# Face.net
KiCad netlist of a schematic drawn in EAGLE
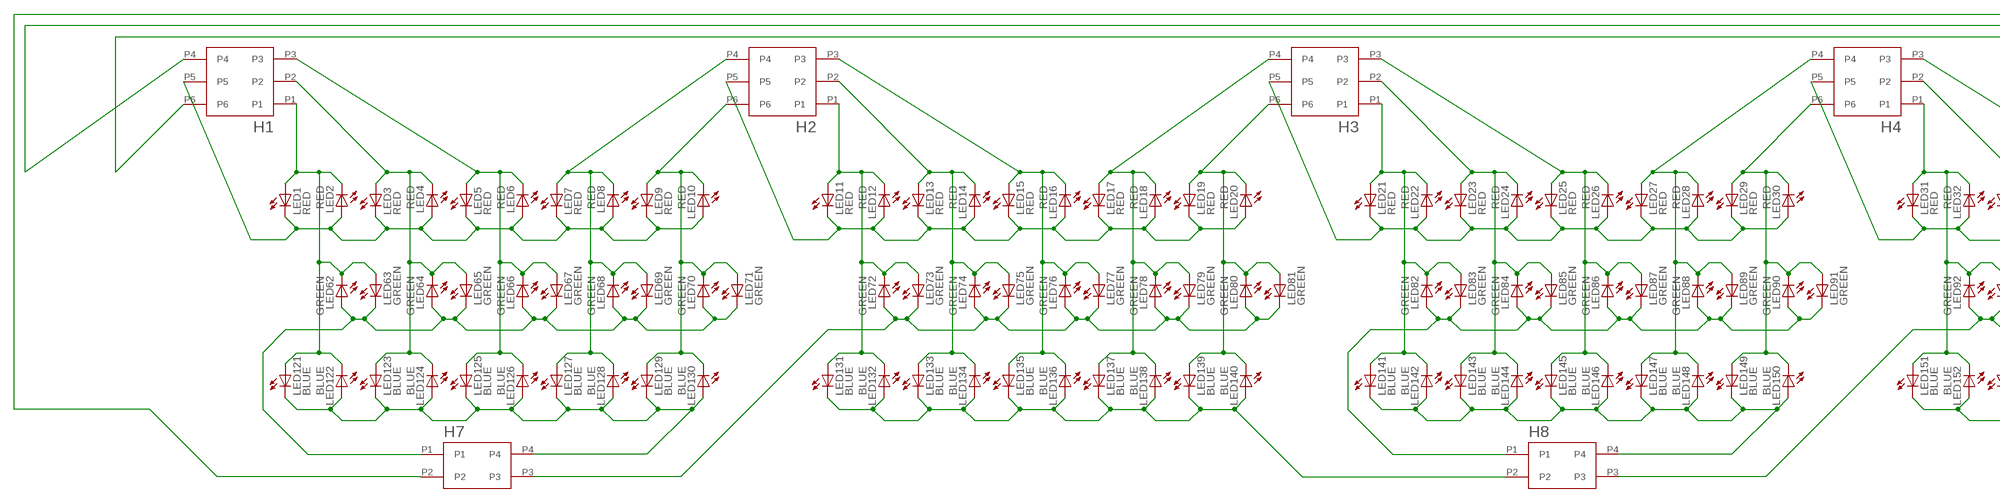
[diagram p0: schematic, sheet 1, part 1 of 2]
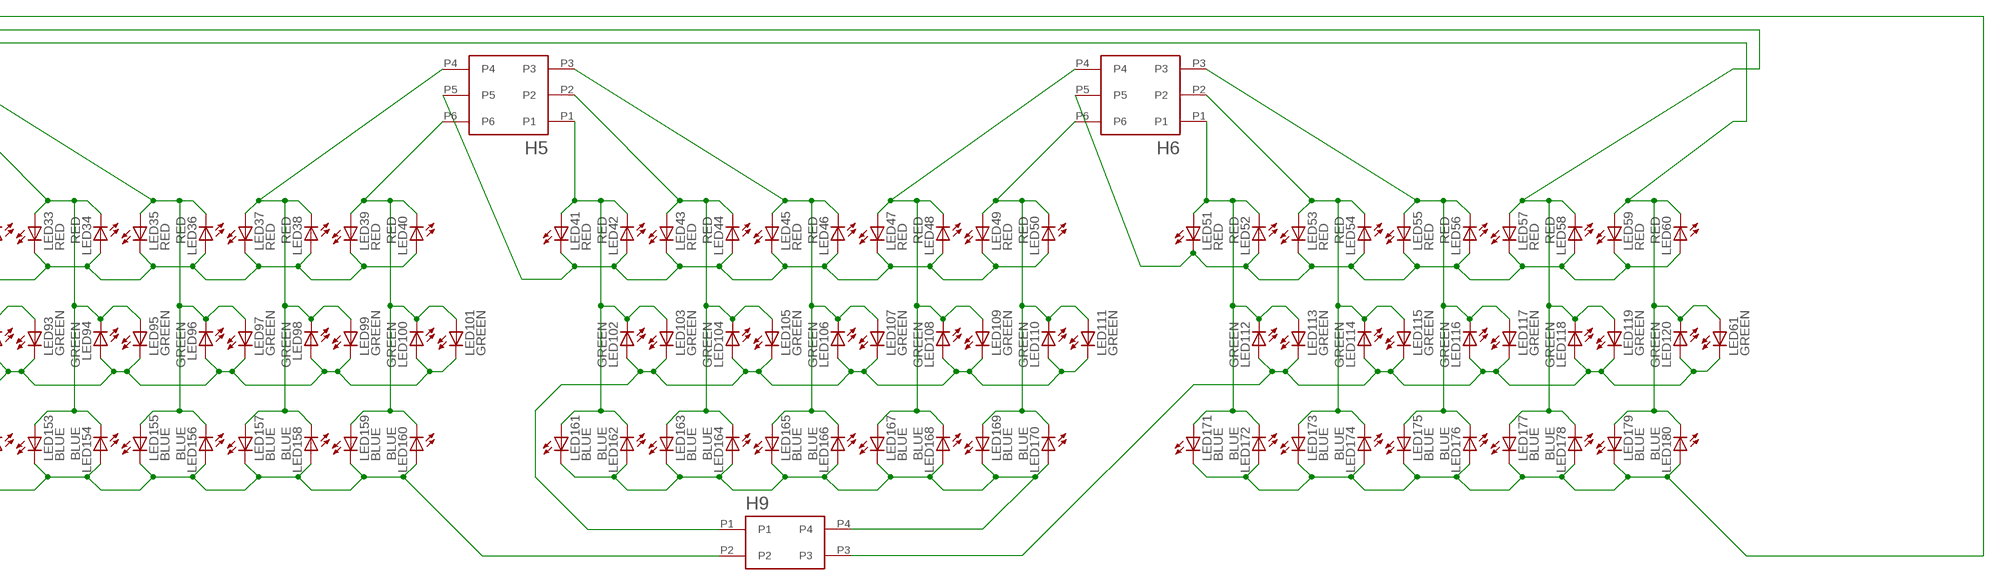
[diagram p1: schematic, sheet 1, part 2 of 2]

(export (version "E")
  (design (tool "Eeschema 10.0.6"))
  (components
    (comp (ref "H1")
      (value "2X3")
      (footprint "eagle-import:3X2_1MM_SMD")
      (libsource (lib "eagle-import") (part "2X3"))
    )
    (comp (ref "H2")
      (value "2X3")
      (footprint "eagle-import:3X2_1MM_SMD")
      (libsource (lib "eagle-import") (part "2X3"))
    )
    (comp (ref "H3")
      (value "2X3")
      (footprint "eagle-import:3X2_1MM_SMD")
      (libsource (lib "eagle-import") (part "2X3"))
    )
    (comp (ref "H4")
      (value "2X3")
      (footprint "eagle-import:3X2_1MM_SMD")
      (libsource (lib "eagle-import") (part "2X3"))
    )
    (comp (ref "H5")
      (value "2X3")
      (footprint "eagle-import:3X2_1MM_SMD")
      (libsource (lib "eagle-import") (part "2X3"))
    )
    (comp (ref "H6")
      (value "2X3")
      (footprint "eagle-import:3X2_1MM_SMD")
      (libsource (lib "eagle-import") (part "2X3"))
    )
    (comp (ref "H7")
      (value "2X2")
      (footprint "eagle-import:2X2_1MM_SMD")
      (libsource (lib "eagle-import") (part "2X2"))
    )
    (comp (ref "H8")
      (value "2X2")
      (footprint "eagle-import:2X2_1MM_SMD")
      (libsource (lib "eagle-import") (part "2X2"))
    )
    (comp (ref "H9")
      (value "2X2")
      (footprint "eagle-import:2X2_1MM_SMD")
      (libsource (lib "eagle-import") (part "2X2"))
    )
    (comp (ref "LED1")
      (value "RED")
      (footprint "eagle-import:LED-0603")
      (libsource (lib "eagle-import") (part "LED0603"))
    )
    (comp (ref "LED2")
      (value "RED")
      (footprint "eagle-import:LED-0603")
      (libsource (lib "eagle-import") (part "LED0603"))
    )
    (comp (ref "LED3")
      (value "RED")
      (footprint "eagle-import:LED-0603")
      (libsource (lib "eagle-import") (part "LED0603"))
    )
    (comp (ref "LED4")
      (value "RED")
      (footprint "eagle-import:LED-0603")
      (libsource (lib "eagle-import") (part "LED0603"))
    )
    (comp (ref "LED5")
      (value "RED")
      (footprint "eagle-import:LED-0603")
      (libsource (lib "eagle-import") (part "LED0603"))
    )
    (comp (ref "LED6")
      (value "RED")
      (footprint "eagle-import:LED-0603")
      (libsource (lib "eagle-import") (part "LED0603"))
    )
    (comp (ref "LED7")
      (value "RED")
      (footprint "eagle-import:LED-0603")
      (libsource (lib "eagle-import") (part "LED0603"))
    )
    (comp (ref "LED8")
      (value "RED")
      (footprint "eagle-import:LED-0603")
      (libsource (lib "eagle-import") (part "LED0603"))
    )
    (comp (ref "LED9")
      (value "RED")
      (footprint "eagle-import:LED-0603")
      (libsource (lib "eagle-import") (part "LED0603"))
    )
    (comp (ref "LED10")
      (value "RED")
      (footprint "eagle-import:LED-0603")
      (libsource (lib "eagle-import") (part "LED0603"))
    )
    (comp (ref "LED11")
      (value "RED")
      (footprint "eagle-import:LED-0603")
      (libsource (lib "eagle-import") (part "LED0603"))
    )
    (comp (ref "LED12")
      (value "RED")
      (footprint "eagle-import:LED-0603")
      (libsource (lib "eagle-import") (part "LED0603"))
    )
    (comp (ref "LED13")
      (value "RED")
      (footprint "eagle-import:LED-0603")
      (libsource (lib "eagle-import") (part "LED0603"))
    )
    (comp (ref "LED14")
      (value "RED")
      (footprint "eagle-import:LED-0603")
      (libsource (lib "eagle-import") (part "LED0603"))
    )
    (comp (ref "LED15")
      (value "RED")
      (footprint "eagle-import:LED-0603")
      (libsource (lib "eagle-import") (part "LED0603"))
    )
    (comp (ref "LED16")
      (value "RED")
      (footprint "eagle-import:LED-0603")
      (libsource (lib "eagle-import") (part "LED0603"))
    )
    (comp (ref "LED17")
      (value "RED")
      (footprint "eagle-import:LED-0603")
      (libsource (lib "eagle-import") (part "LED0603"))
    )
    (comp (ref "LED18")
      (value "RED")
      (footprint "eagle-import:LED-0603")
      (libsource (lib "eagle-import") (part "LED0603"))
    )
    (comp (ref "LED19")
      (value "RED")
      (footprint "eagle-import:LED-0603")
      (libsource (lib "eagle-import") (part "LED0603"))
    )
    (comp (ref "LED20")
      (value "RED")
      (footprint "eagle-import:LED-0603")
      (libsource (lib "eagle-import") (part "LED0603"))
    )
    (comp (ref "LED21")
      (value "RED")
      (footprint "eagle-import:LED-0603")
      (libsource (lib "eagle-import") (part "LED0603"))
    )
    (comp (ref "LED22")
      (value "RED")
      (footprint "eagle-import:LED-0603")
      (libsource (lib "eagle-import") (part "LED0603"))
    )
    (comp (ref "LED23")
      (value "RED")
      (footprint "eagle-import:LED-0603")
      (libsource (lib "eagle-import") (part "LED0603"))
    )
    (comp (ref "LED24")
      (value "RED")
      (footprint "eagle-import:LED-0603")
      (libsource (lib "eagle-import") (part "LED0603"))
    )
    (comp (ref "LED25")
      (value "RED")
      (footprint "eagle-import:LED-0603")
      (libsource (lib "eagle-import") (part "LED0603"))
    )
    (comp (ref "LED26")
      (value "RED")
      (footprint "eagle-import:LED-0603")
      (libsource (lib "eagle-import") (part "LED0603"))
    )
    (comp (ref "LED27")
      (value "RED")
      (footprint "eagle-import:LED-0603")
      (libsource (lib "eagle-import") (part "LED0603"))
    )
    (comp (ref "LED28")
      (value "RED")
      (footprint "eagle-import:LED-0603")
      (libsource (lib "eagle-import") (part "LED0603"))
    )
    (comp (ref "LED29")
      (value "RED")
      (footprint "eagle-import:LED-0603")
      (libsource (lib "eagle-import") (part "LED0603"))
    )
    (comp (ref "LED30")
      (value "RED")
      (footprint "eagle-import:LED-0603")
      (libsource (lib "eagle-import") (part "LED0603"))
    )
    (comp (ref "LED31")
      (value "RED")
      (footprint "eagle-import:LED-0603")
      (libsource (lib "eagle-import") (part "LED0603"))
    )
    (comp (ref "LED32")
      (value "RED")
      (footprint "eagle-import:LED-0603")
      (libsource (lib "eagle-import") (part "LED0603"))
    )
    (comp (ref "LED33")
      (value "RED")
      (footprint "eagle-import:LED-0603")
      (libsource (lib "eagle-import") (part "LED0603"))
    )
    (comp (ref "LED34")
      (value "RED")
      (footprint "eagle-import:LED-0603")
      (libsource (lib "eagle-import") (part "LED0603"))
    )
    (comp (ref "LED35")
      (value "RED")
      (footprint "eagle-import:LED-0603")
      (libsource (lib "eagle-import") (part "LED0603"))
    )
    (comp (ref "LED36")
      (value "RED")
      (footprint "eagle-import:LED-0603")
      (libsource (lib "eagle-import") (part "LED0603"))
    )
    (comp (ref "LED37")
      (value "RED")
      (footprint "eagle-import:LED-0603")
      (libsource (lib "eagle-import") (part "LED0603"))
    )
    (comp (ref "LED38")
      (value "RED")
      (footprint "eagle-import:LED-0603")
      (libsource (lib "eagle-import") (part "LED0603"))
    )
    (comp (ref "LED39")
      (value "RED")
      (footprint "eagle-import:LED-0603")
      (libsource (lib "eagle-import") (part "LED0603"))
    )
    (comp (ref "LED40")
      (value "RED")
      (footprint "eagle-import:LED-0603")
      (libsource (lib "eagle-import") (part "LED0603"))
    )
    (comp (ref "LED41")
      (value "RED")
      (footprint "eagle-import:LED-0603")
      (libsource (lib "eagle-import") (part "LED0603"))
    )
    (comp (ref "LED42")
      (value "RED")
      (footprint "eagle-import:LED-0603")
      (libsource (lib "eagle-import") (part "LED0603"))
    )
    (comp (ref "LED43")
      (value "RED")
      (footprint "eagle-import:LED-0603")
      (libsource (lib "eagle-import") (part "LED0603"))
    )
    (comp (ref "LED44")
      (value "RED")
      (footprint "eagle-import:LED-0603")
      (libsource (lib "eagle-import") (part "LED0603"))
    )
    (comp (ref "LED45")
      (value "RED")
      (footprint "eagle-import:LED-0603")
      (libsource (lib "eagle-import") (part "LED0603"))
    )
    (comp (ref "LED46")
      (value "RED")
      (footprint "eagle-import:LED-0603")
      (libsource (lib "eagle-import") (part "LED0603"))
    )
    (comp (ref "LED47")
      (value "RED")
      (footprint "eagle-import:LED-0603")
      (libsource (lib "eagle-import") (part "LED0603"))
    )
    (comp (ref "LED48")
      (value "RED")
      (footprint "eagle-import:LED-0603")
      (libsource (lib "eagle-import") (part "LED0603"))
    )
    (comp (ref "LED49")
      (value "RED")
      (footprint "eagle-import:LED-0603")
      (libsource (lib "eagle-import") (part "LED0603"))
    )
    (comp (ref "LED50")
      (value "RED")
      (footprint "eagle-import:LED-0603")
      (libsource (lib "eagle-import") (part "LED0603"))
    )
    (comp (ref "LED51")
      (value "RED")
      (footprint "eagle-import:LED-0603")
      (libsource (lib "eagle-import") (part "LED0603"))
    )
    (comp (ref "LED52")
      (value "RED")
      (footprint "eagle-import:LED-0603")
      (libsource (lib "eagle-import") (part "LED0603"))
    )
    (comp (ref "LED53")
      (value "RED")
      (footprint "eagle-import:LED-0603")
      (libsource (lib "eagle-import") (part "LED0603"))
    )
    (comp (ref "LED54")
      (value "RED")
      (footprint "eagle-import:LED-0603")
      (libsource (lib "eagle-import") (part "LED0603"))
    )
    (comp (ref "LED55")
      (value "RED")
      (footprint "eagle-import:LED-0603")
      (libsource (lib "eagle-import") (part "LED0603"))
    )
    (comp (ref "LED56")
      (value "RED")
      (footprint "eagle-import:LED-0603")
      (libsource (lib "eagle-import") (part "LED0603"))
    )
    (comp (ref "LED57")
      (value "RED")
      (footprint "eagle-import:LED-0603")
      (libsource (lib "eagle-import") (part "LED0603"))
    )
    (comp (ref "LED58")
      (value "RED")
      (footprint "eagle-import:LED-0603")
      (libsource (lib "eagle-import") (part "LED0603"))
    )
    (comp (ref "LED59")
      (value "RED")
      (footprint "eagle-import:LED-0603")
      (libsource (lib "eagle-import") (part "LED0603"))
    )
    (comp (ref "LED60")
      (value "RED")
      (footprint "eagle-import:LED-0603")
      (libsource (lib "eagle-import") (part "LED0603"))
    )
    (comp (ref "LED61")
      (value "GREEN")
      (footprint "eagle-import:LED-0603")
      (libsource (lib "eagle-import") (part "LED0603"))
    )
    (comp (ref "LED62")
      (value "GREEN")
      (footprint "eagle-import:LED-0603")
      (libsource (lib "eagle-import") (part "LED0603"))
    )
    (comp (ref "LED63")
      (value "GREEN")
      (footprint "eagle-import:LED-0603")
      (libsource (lib "eagle-import") (part "LED0603"))
    )
    (comp (ref "LED64")
      (value "GREEN")
      (footprint "eagle-import:LED-0603")
      (libsource (lib "eagle-import") (part "LED0603"))
    )
    (comp (ref "LED65")
      (value "GREEN")
      (footprint "eagle-import:LED-0603")
      (libsource (lib "eagle-import") (part "LED0603"))
    )
    (comp (ref "LED66")
      (value "GREEN")
      (footprint "eagle-import:LED-0603")
      (libsource (lib "eagle-import") (part "LED0603"))
    )
    (comp (ref "LED67")
      (value "GREEN")
      (footprint "eagle-import:LED-0603")
      (libsource (lib "eagle-import") (part "LED0603"))
    )
    (comp (ref "LED68")
      (value "GREEN")
      (footprint "eagle-import:LED-0603")
      (libsource (lib "eagle-import") (part "LED0603"))
    )
    (comp (ref "LED69")
      (value "GREEN")
      (footprint "eagle-import:LED-0603")
      (libsource (lib "eagle-import") (part "LED0603"))
    )
    (comp (ref "LED70")
      (value "GREEN")
      (footprint "eagle-import:LED-0603")
      (libsource (lib "eagle-import") (part "LED0603"))
    )
    (comp (ref "LED71")
      (value "GREEN")
      (footprint "eagle-import:LED-0603")
      (libsource (lib "eagle-import") (part "LED0603"))
    )
    (comp (ref "LED72")
      (value "GREEN")
      (footprint "eagle-import:LED-0603")
      (libsource (lib "eagle-import") (part "LED0603"))
    )
    (comp (ref "LED73")
      (value "GREEN")
      (footprint "eagle-import:LED-0603")
      (libsource (lib "eagle-import") (part "LED0603"))
    )
    (comp (ref "LED74")
      (value "GREEN")
      (footprint "eagle-import:LED-0603")
      (libsource (lib "eagle-import") (part "LED0603"))
    )
    (comp (ref "LED75")
      (value "GREEN")
      (footprint "eagle-import:LED-0603")
      (libsource (lib "eagle-import") (part "LED0603"))
    )
    (comp (ref "LED76")
      (value "GREEN")
      (footprint "eagle-import:LED-0603")
      (libsource (lib "eagle-import") (part "LED0603"))
    )
    (comp (ref "LED77")
      (value "GREEN")
      (footprint "eagle-import:LED-0603")
      (libsource (lib "eagle-import") (part "LED0603"))
    )
    (comp (ref "LED78")
      (value "GREEN")
      (footprint "eagle-import:LED-0603")
      (libsource (lib "eagle-import") (part "LED0603"))
    )
    (comp (ref "LED79")
      (value "GREEN")
      (footprint "eagle-import:LED-0603")
      (libsource (lib "eagle-import") (part "LED0603"))
    )
    (comp (ref "LED80")
      (value "GREEN")
      (footprint "eagle-import:LED-0603")
      (libsource (lib "eagle-import") (part "LED0603"))
    )
    (comp (ref "LED81")
      (value "GREEN")
      (footprint "eagle-import:LED-0603")
      (libsource (lib "eagle-import") (part "LED0603"))
    )
    (comp (ref "LED82")
      (value "GREEN")
      (footprint "eagle-import:LED-0603")
      (libsource (lib "eagle-import") (part "LED0603"))
    )
    (comp (ref "LED83")
      (value "GREEN")
      (footprint "eagle-import:LED-0603")
      (libsource (lib "eagle-import") (part "LED0603"))
    )
    (comp (ref "LED84")
      (value "GREEN")
      (footprint "eagle-import:LED-0603")
      (libsource (lib "eagle-import") (part "LED0603"))
    )
    (comp (ref "LED85")
      (value "GREEN")
      (footprint "eagle-import:LED-0603")
      (libsource (lib "eagle-import") (part "LED0603"))
    )
    (comp (ref "LED86")
      (value "GREEN")
      (footprint "eagle-import:LED-0603")
      (libsource (lib "eagle-import") (part "LED0603"))
    )
    (comp (ref "LED87")
      (value "GREEN")
      (footprint "eagle-import:LED-0603")
      (libsource (lib "eagle-import") (part "LED0603"))
    )
    (comp (ref "LED88")
      (value "GREEN")
      (footprint "eagle-import:LED-0603")
      (libsource (lib "eagle-import") (part "LED0603"))
    )
    (comp (ref "LED89")
      (value "GREEN")
      (footprint "eagle-import:LED-0603")
      (libsource (lib "eagle-import") (part "LED0603"))
    )
    (comp (ref "LED90")
      (value "GREEN")
      (footprint "eagle-import:LED-0603")
      (libsource (lib "eagle-import") (part "LED0603"))
    )
    (comp (ref "LED91")
      (value "GREEN")
      (footprint "eagle-import:LED-0603")
      (libsource (lib "eagle-import") (part "LED0603"))
    )
    (comp (ref "LED92")
      (value "GREEN")
      (footprint "eagle-import:LED-0603")
      (libsource (lib "eagle-import") (part "LED0603"))
    )
    (comp (ref "LED93")
      (value "GREEN")
      (footprint "eagle-import:LED-0603")
      (libsource (lib "eagle-import") (part "LED0603"))
    )
    (comp (ref "LED94")
      (value "GREEN")
      (footprint "eagle-import:LED-0603")
      (libsource (lib "eagle-import") (part "LED0603"))
    )
    (comp (ref "LED95")
      (value "GREEN")
      (footprint "eagle-import:LED-0603")
      (libsource (lib "eagle-import") (part "LED0603"))
    )
    (comp (ref "LED96")
      (value "GREEN")
      (footprint "eagle-import:LED-0603")
      (libsource (lib "eagle-import") (part "LED0603"))
    )
    (comp (ref "LED97")
      (value "GREEN")
      (footprint "eagle-import:LED-0603")
      (libsource (lib "eagle-import") (part "LED0603"))
    )
    (comp (ref "LED98")
      (value "GREEN")
      (footprint "eagle-import:LED-0603")
      (libsource (lib "eagle-import") (part "LED0603"))
    )
    (comp (ref "LED99")
      (value "GREEN")
      (footprint "eagle-import:LED-0603")
      (libsource (lib "eagle-import") (part "LED0603"))
    )
    (comp (ref "LED100")
      (value "GREEN")
      (footprint "eagle-import:LED-0603")
      (libsource (lib "eagle-import") (part "LED0603"))
    )
    (comp (ref "LED101")
      (value "GREEN")
      (footprint "eagle-import:LED-0603")
      (libsource (lib "eagle-import") (part "LED0603"))
    )
    (comp (ref "LED102")
      (value "GREEN")
      (footprint "eagle-import:LED-0603")
      (libsource (lib "eagle-import") (part "LED0603"))
    )
    (comp (ref "LED103")
      (value "GREEN")
      (footprint "eagle-import:LED-0603")
      (libsource (lib "eagle-import") (part "LED0603"))
    )
    (comp (ref "LED104")
      (value "GREEN")
      (footprint "eagle-import:LED-0603")
      (libsource (lib "eagle-import") (part "LED0603"))
    )
    (comp (ref "LED105")
      (value "GREEN")
      (footprint "eagle-import:LED-0603")
      (libsource (lib "eagle-import") (part "LED0603"))
    )
    (comp (ref "LED106")
      (value "GREEN")
      (footprint "eagle-import:LED-0603")
      (libsource (lib "eagle-import") (part "LED0603"))
    )
    (comp (ref "LED107")
      (value "GREEN")
      (footprint "eagle-import:LED-0603")
      (libsource (lib "eagle-import") (part "LED0603"))
    )
    (comp (ref "LED108")
      (value "GREEN")
      (footprint "eagle-import:LED-0603")
      (libsource (lib "eagle-import") (part "LED0603"))
    )
    (comp (ref "LED109")
      (value "GREEN")
      (footprint "eagle-import:LED-0603")
      (libsource (lib "eagle-import") (part "LED0603"))
    )
    (comp (ref "LED110")
      (value "GREEN")
      (footprint "eagle-import:LED-0603")
      (libsource (lib "eagle-import") (part "LED0603"))
    )
    (comp (ref "LED111")
      (value "GREEN")
      (footprint "eagle-import:LED-0603")
      (libsource (lib "eagle-import") (part "LED0603"))
    )
    (comp (ref "LED112")
      (value "GREEN")
      (footprint "eagle-import:LED-0603")
      (libsource (lib "eagle-import") (part "LED0603"))
    )
    (comp (ref "LED113")
      (value "GREEN")
      (footprint "eagle-import:LED-0603")
      (libsource (lib "eagle-import") (part "LED0603"))
    )
    (comp (ref "LED114")
      (value "GREEN")
      (footprint "eagle-import:LED-0603")
      (libsource (lib "eagle-import") (part "LED0603"))
    )
    (comp (ref "LED115")
      (value "GREEN")
      (footprint "eagle-import:LED-0603")
      (libsource (lib "eagle-import") (part "LED0603"))
    )
    (comp (ref "LED116")
      (value "GREEN")
      (footprint "eagle-import:LED-0603")
      (libsource (lib "eagle-import") (part "LED0603"))
    )
    (comp (ref "LED117")
      (value "GREEN")
      (footprint "eagle-import:LED-0603")
      (libsource (lib "eagle-import") (part "LED0603"))
    )
    (comp (ref "LED118")
      (value "GREEN")
      (footprint "eagle-import:LED-0603")
      (libsource (lib "eagle-import") (part "LED0603"))
    )
    (comp (ref "LED119")
      (value "GREEN")
      (footprint "eagle-import:LED-0603")
      (libsource (lib "eagle-import") (part "LED0603"))
    )
    (comp (ref "LED120")
      (value "GREEN")
      (footprint "eagle-import:LED-0603")
      (libsource (lib "eagle-import") (part "LED0603"))
    )
    (comp (ref "LED121")
      (value "BLUE")
      (footprint "eagle-import:LED-0603")
      (libsource (lib "eagle-import") (part "LED0603"))
    )
    (comp (ref "LED122")
      (value "BLUE")
      (footprint "eagle-import:LED-0603")
      (libsource (lib "eagle-import") (part "LED0603"))
    )
    (comp (ref "LED123")
      (value "BLUE")
      (footprint "eagle-import:LED-0603")
      (libsource (lib "eagle-import") (part "LED0603"))
    )
    (comp (ref "LED124")
      (value "BLUE")
      (footprint "eagle-import:LED-0603")
      (libsource (lib "eagle-import") (part "LED0603"))
    )
    (comp (ref "LED125")
      (value "BLUE")
      (footprint "eagle-import:LED-0603")
      (libsource (lib "eagle-import") (part "LED0603"))
    )
    (comp (ref "LED126")
      (value "BLUE")
      (footprint "eagle-import:LED-0603")
      (libsource (lib "eagle-import") (part "LED0603"))
    )
    (comp (ref "LED127")
      (value "BLUE")
      (footprint "eagle-import:LED-0603")
      (libsource (lib "eagle-import") (part "LED0603"))
    )
    (comp (ref "LED128")
      (value "BLUE")
      (footprint "eagle-import:LED-0603")
      (libsource (lib "eagle-import") (part "LED0603"))
    )
    (comp (ref "LED129")
      (value "BLUE")
      (footprint "eagle-import:LED-0603")
      (libsource (lib "eagle-import") (part "LED0603"))
    )
    (comp (ref "LED130")
      (value "BLUE")
      (footprint "eagle-import:LED-0603")
      (libsource (lib "eagle-import") (part "LED0603"))
    )
    (comp (ref "LED131")
      (value "BLUE")
      (footprint "eagle-import:LED-0603")
      (libsource (lib "eagle-import") (part "LED0603"))
    )
    (comp (ref "LED132")
      (value "BLUE")
      (footprint "eagle-import:LED-0603")
      (libsource (lib "eagle-import") (part "LED0603"))
    )
    (comp (ref "LED133")
      (value "BLUE")
      (footprint "eagle-import:LED-0603")
      (libsource (lib "eagle-import") (part "LED0603"))
    )
    (comp (ref "LED134")
      (value "BLUE")
      (footprint "eagle-import:LED-0603")
      (libsource (lib "eagle-import") (part "LED0603"))
    )
    (comp (ref "LED135")
      (value "BLUE")
      (footprint "eagle-import:LED-0603")
      (libsource (lib "eagle-import") (part "LED0603"))
    )
    (comp (ref "LED136")
      (value "BLUE")
      (footprint "eagle-import:LED-0603")
      (libsource (lib "eagle-import") (part "LED0603"))
    )
    (comp (ref "LED137")
      (value "BLUE")
      (footprint "eagle-import:LED-0603")
      (libsource (lib "eagle-import") (part "LED0603"))
    )
    (comp (ref "LED138")
      (value "BLUE")
      (footprint "eagle-import:LED-0603")
      (libsource (lib "eagle-import") (part "LED0603"))
    )
    (comp (ref "LED139")
      (value "BLUE")
      (footprint "eagle-import:LED-0603")
      (libsource (lib "eagle-import") (part "LED0603"))
    )
    (comp (ref "LED140")
      (value "BLUE")
      (footprint "eagle-import:LED-0603")
      (libsource (lib "eagle-import") (part "LED0603"))
    )
    (comp (ref "LED141")
      (value "BLUE")
      (footprint "eagle-import:LED-0603")
      (libsource (lib "eagle-import") (part "LED0603"))
    )
    (comp (ref "LED142")
      (value "BLUE")
      (footprint "eagle-import:LED-0603")
      (libsource (lib "eagle-import") (part "LED0603"))
    )
    (comp (ref "LED143")
      (value "BLUE")
      (footprint "eagle-import:LED-0603")
      (libsource (lib "eagle-import") (part "LED0603"))
    )
    (comp (ref "LED144")
      (value "BLUE")
      (footprint "eagle-import:LED-0603")
      (libsource (lib "eagle-import") (part "LED0603"))
    )
    (comp (ref "LED145")
      (value "BLUE")
      (footprint "eagle-import:LED-0603")
      (libsource (lib "eagle-import") (part "LED0603"))
    )
    (comp (ref "LED146")
      (value "BLUE")
      (footprint "eagle-import:LED-0603")
      (libsource (lib "eagle-import") (part "LED0603"))
    )
    (comp (ref "LED147")
      (value "BLUE")
      (footprint "eagle-import:LED-0603")
      (libsource (lib "eagle-import") (part "LED0603"))
    )
    (comp (ref "LED148")
      (value "BLUE")
      (footprint "eagle-import:LED-0603")
      (libsource (lib "eagle-import") (part "LED0603"))
    )
    (comp (ref "LED149")
      (value "BLUE")
      (footprint "eagle-import:LED-0603")
      (libsource (lib "eagle-import") (part "LED0603"))
    )
    (comp (ref "LED150")
      (value "BLUE")
      (footprint "eagle-import:LED-0603")
      (libsource (lib "eagle-import") (part "LED0603"))
    )
    (comp (ref "LED151")
      (value "BLUE")
      (footprint "eagle-import:LED-0603")
      (libsource (lib "eagle-import") (part "LED0603"))
    )
    (comp (ref "LED152")
      (value "BLUE")
      (footprint "eagle-import:LED-0603")
      (libsource (lib "eagle-import") (part "LED0603"))
    )
    (comp (ref "LED153")
      (value "BLUE")
      (footprint "eagle-import:LED-0603")
      (libsource (lib "eagle-import") (part "LED0603"))
    )
    (comp (ref "LED154")
      (value "BLUE")
      (footprint "eagle-import:LED-0603")
      (libsource (lib "eagle-import") (part "LED0603"))
    )
    (comp (ref "LED155")
      (value "BLUE")
      (footprint "eagle-import:LED-0603")
      (libsource (lib "eagle-import") (part "LED0603"))
    )
    (comp (ref "LED156")
      (value "BLUE")
      (footprint "eagle-import:LED-0603")
      (libsource (lib "eagle-import") (part "LED0603"))
    )
    (comp (ref "LED157")
      (value "BLUE")
      (footprint "eagle-import:LED-0603")
      (libsource (lib "eagle-import") (part "LED0603"))
    )
    (comp (ref "LED158")
      (value "BLUE")
      (footprint "eagle-import:LED-0603")
      (libsource (lib "eagle-import") (part "LED0603"))
    )
    (comp (ref "LED159")
      (value "BLUE")
      (footprint "eagle-import:LED-0603")
      (libsource (lib "eagle-import") (part "LED0603"))
    )
    (comp (ref "LED160")
      (value "BLUE")
      (footprint "eagle-import:LED-0603")
      (libsource (lib "eagle-import") (part "LED0603"))
    )
    (comp (ref "LED161")
      (value "BLUE")
      (footprint "eagle-import:LED-0603")
      (libsource (lib "eagle-import") (part "LED0603"))
    )
    (comp (ref "LED162")
      (value "BLUE")
      (footprint "eagle-import:LED-0603")
      (libsource (lib "eagle-import") (part "LED0603"))
    )
    (comp (ref "LED163")
      (value "BLUE")
      (footprint "eagle-import:LED-0603")
      (libsource (lib "eagle-import") (part "LED0603"))
    )
    (comp (ref "LED164")
      (value "BLUE")
      (footprint "eagle-import:LED-0603")
      (libsource (lib "eagle-import") (part "LED0603"))
    )
    (comp (ref "LED165")
      (value "BLUE")
      (footprint "eagle-import:LED-0603")
      (libsource (lib "eagle-import") (part "LED0603"))
    )
    (comp (ref "LED166")
      (value "BLUE")
      (footprint "eagle-import:LED-0603")
      (libsource (lib "eagle-import") (part "LED0603"))
    )
    (comp (ref "LED167")
      (value "BLUE")
      (footprint "eagle-import:LED-0603")
      (libsource (lib "eagle-import") (part "LED0603"))
    )
    (comp (ref "LED168")
      (value "BLUE")
      (footprint "eagle-import:LED-0603")
      (libsource (lib "eagle-import") (part "LED0603"))
    )
    (comp (ref "LED169")
      (value "BLUE")
      (footprint "eagle-import:LED-0603")
      (libsource (lib "eagle-import") (part "LED0603"))
    )
    (comp (ref "LED170")
      (value "BLUE")
      (footprint "eagle-import:LED-0603")
      (libsource (lib "eagle-import") (part "LED0603"))
    )
    (comp (ref "LED171")
      (value "BLUE")
      (footprint "eagle-import:LED-0603")
      (libsource (lib "eagle-import") (part "LED0603"))
    )
    (comp (ref "LED172")
      (value "BLUE")
      (footprint "eagle-import:LED-0603")
      (libsource (lib "eagle-import") (part "LED0603"))
    )
    (comp (ref "LED173")
      (value "BLUE")
      (footprint "eagle-import:LED-0603")
      (libsource (lib "eagle-import") (part "LED0603"))
    )
    (comp (ref "LED174")
      (value "BLUE")
      (footprint "eagle-import:LED-0603")
      (libsource (lib "eagle-import") (part "LED0603"))
    )
    (comp (ref "LED175")
      (value "BLUE")
      (footprint "eagle-import:LED-0603")
      (libsource (lib "eagle-import") (part "LED0603"))
    )
    (comp (ref "LED176")
      (value "BLUE")
      (footprint "eagle-import:LED-0603")
      (libsource (lib "eagle-import") (part "LED0603"))
    )
    (comp (ref "LED177")
      (value "BLUE")
      (footprint "eagle-import:LED-0603")
      (libsource (lib "eagle-import") (part "LED0603"))
    )
    (comp (ref "LED178")
      (value "BLUE")
      (footprint "eagle-import:LED-0603")
      (libsource (lib "eagle-import") (part "LED0603"))
    )
    (comp (ref "LED179")
      (value "BLUE")
      (footprint "eagle-import:LED-0603")
      (libsource (lib "eagle-import") (part "LED0603"))
    )
    (comp (ref "LED180")
      (value "BLUE")
      (footprint "eagle-import:LED-0603")
      (libsource (lib "eagle-import") (part "LED0603"))
    )
  )
  (nets
    (net (code "1") (name "Net-(H1-PadP1)") (class "Default")
      (node (ref "H1") (pin "P1") (pinfunction "P1_P1") (pintype "bidirectional"))
      (node (ref "LED1") (pin "A") (pinfunction "A_A") (pintype "passive"))
      (node (ref "LED121") (pin "A") (pinfunction "A_A") (pintype "passive"))
      (node (ref "LED122") (pin "C") (pinfunction "C_C") (pintype "passive"))
      (node (ref "LED2") (pin "C") (pinfunction "C_C") (pintype "passive"))
      (node (ref "LED62") (pin "C") (pinfunction "C_C") (pintype "passive"))
      (node (ref "LED63") (pin "A") (pinfunction "A_A") (pintype "passive"))
    )
    (net (code "2") (name "Net-(H1-PadP2)") (class "Default")
      (node (ref "H1") (pin "P2") (pinfunction "P2_P2") (pintype "bidirectional"))
      (node (ref "LED123") (pin "A") (pinfunction "A_A") (pintype "passive"))
      (node (ref "LED124") (pin "C") (pinfunction "C_C") (pintype "passive"))
      (node (ref "LED3") (pin "A") (pinfunction "A_A") (pintype "passive"))
      (node (ref "LED4") (pin "C") (pinfunction "C_C") (pintype "passive"))
      (node (ref "LED64") (pin "C") (pinfunction "C_C") (pintype "passive"))
      (node (ref "LED65") (pin "A") (pinfunction "A_A") (pintype "passive"))
    )
    (net (code "3") (name "Net-(H1-PadP3)") (class "Default")
      (node (ref "H1") (pin "P3") (pinfunction "P3_P3") (pintype "bidirectional"))
      (node (ref "LED125") (pin "A") (pinfunction "A_A") (pintype "passive"))
      (node (ref "LED126") (pin "C") (pinfunction "C_C") (pintype "passive"))
      (node (ref "LED5") (pin "A") (pinfunction "A_A") (pintype "passive"))
      (node (ref "LED6") (pin "C") (pinfunction "C_C") (pintype "passive"))
      (node (ref "LED66") (pin "C") (pinfunction "C_C") (pintype "passive"))
      (node (ref "LED67") (pin "A") (pinfunction "A_A") (pintype "passive"))
    )
    (net (code "4") (name "Net-(H1-PadP4)") (class "Default")
      (node (ref "H1") (pin "P4") (pinfunction "P4_P4") (pintype "bidirectional"))
      (node (ref "LED118") (pin "C") (pinfunction "C_C") (pintype "passive"))
      (node (ref "LED119") (pin "A") (pinfunction "A_A") (pintype "passive"))
      (node (ref "LED177") (pin "A") (pinfunction "A_A") (pintype "passive"))
      (node (ref "LED178") (pin "C") (pinfunction "C_C") (pintype "passive"))
      (node (ref "LED57") (pin "A") (pinfunction "A_A") (pintype "passive"))
      (node (ref "LED58") (pin "C") (pinfunction "C_C") (pintype "passive"))
    )
    (net (code "5") (name "Net-(H1-PadP5)") (class "Default")
      (node (ref "H1") (pin "P5") (pinfunction "P5_P5") (pintype "bidirectional"))
      (node (ref "LED1") (pin "C") (pinfunction "C_C") (pintype "passive"))
      (node (ref "LED10") (pin "A") (pinfunction "A_A") (pintype "passive"))
      (node (ref "LED2") (pin "A") (pinfunction "A_A") (pintype "passive"))
      (node (ref "LED3") (pin "C") (pinfunction "C_C") (pintype "passive"))
      (node (ref "LED4") (pin "A") (pinfunction "A_A") (pintype "passive"))
      (node (ref "LED5") (pin "C") (pinfunction "C_C") (pintype "passive"))
      (node (ref "LED6") (pin "A") (pinfunction "A_A") (pintype "passive"))
      (node (ref "LED7") (pin "C") (pinfunction "C_C") (pintype "passive"))
      (node (ref "LED8") (pin "A") (pinfunction "A_A") (pintype "passive"))
      (node (ref "LED9") (pin "C") (pinfunction "C_C") (pintype "passive"))
    )
    (net (code "6") (name "Net-(H1-PadP6)") (class "Default")
      (node (ref "H1") (pin "P6") (pinfunction "P6_P6") (pintype "bidirectional"))
      (node (ref "LED120") (pin "C") (pinfunction "C_C") (pintype "passive"))
      (node (ref "LED179") (pin "A") (pinfunction "A_A") (pintype "passive"))
      (node (ref "LED180") (pin "C") (pinfunction "C_C") (pintype "passive"))
      (node (ref "LED59") (pin "A") (pinfunction "A_A") (pintype "passive"))
      (node (ref "LED60") (pin "C") (pinfunction "C_C") (pintype "passive"))
      (node (ref "LED61") (pin "A") (pinfunction "A_A") (pintype "passive"))
    )
    (net (code "7") (name "Net-(H2-PadP1)") (class "Default")
      (node (ref "H2") (pin "P1") (pinfunction "P1_P1") (pintype "bidirectional"))
      (node (ref "LED11") (pin "A") (pinfunction "A_A") (pintype "passive"))
      (node (ref "LED12") (pin "C") (pinfunction "C_C") (pintype "passive"))
      (node (ref "LED131") (pin "A") (pinfunction "A_A") (pintype "passive"))
      (node (ref "LED132") (pin "C") (pinfunction "C_C") (pintype "passive"))
      (node (ref "LED72") (pin "C") (pinfunction "C_C") (pintype "passive"))
      (node (ref "LED73") (pin "A") (pinfunction "A_A") (pintype "passive"))
    )
    (net (code "8") (name "Net-(H2-PadP2)") (class "Default")
      (node (ref "H2") (pin "P2") (pinfunction "P2_P2") (pintype "bidirectional"))
      (node (ref "LED13") (pin "A") (pinfunction "A_A") (pintype "passive"))
      (node (ref "LED133") (pin "A") (pinfunction "A_A") (pintype "passive"))
      (node (ref "LED134") (pin "C") (pinfunction "C_C") (pintype "passive"))
      (node (ref "LED14") (pin "C") (pinfunction "C_C") (pintype "passive"))
      (node (ref "LED74") (pin "C") (pinfunction "C_C") (pintype "passive"))
      (node (ref "LED75") (pin "A") (pinfunction "A_A") (pintype "passive"))
    )
    (net (code "9") (name "Net-(H2-PadP3)") (class "Default")
      (node (ref "H2") (pin "P3") (pinfunction "P3_P3") (pintype "bidirectional"))
      (node (ref "LED135") (pin "A") (pinfunction "A_A") (pintype "passive"))
      (node (ref "LED136") (pin "C") (pinfunction "C_C") (pintype "passive"))
      (node (ref "LED15") (pin "A") (pinfunction "A_A") (pintype "passive"))
      (node (ref "LED16") (pin "C") (pinfunction "C_C") (pintype "passive"))
      (node (ref "LED76") (pin "C") (pinfunction "C_C") (pintype "passive"))
      (node (ref "LED77") (pin "A") (pinfunction "A_A") (pintype "passive"))
    )
    (net (code "10") (name "Net-(H2-PadP4)") (class "Default")
      (node (ref "H2") (pin "P4") (pinfunction "P4_P4") (pintype "bidirectional"))
      (node (ref "LED127") (pin "A") (pinfunction "A_A") (pintype "passive"))
      (node (ref "LED128") (pin "C") (pinfunction "C_C") (pintype "passive"))
      (node (ref "LED68") (pin "C") (pinfunction "C_C") (pintype "passive"))
      (node (ref "LED69") (pin "A") (pinfunction "A_A") (pintype "passive"))
      (node (ref "LED7") (pin "A") (pinfunction "A_A") (pintype "passive"))
      (node (ref "LED8") (pin "C") (pinfunction "C_C") (pintype "passive"))
    )
    (net (code "11") (name "Net-(H2-PadP5)") (class "Default")
      (node (ref "H2") (pin "P5") (pinfunction "P5_P5") (pintype "bidirectional"))
      (node (ref "LED11") (pin "C") (pinfunction "C_C") (pintype "passive"))
      (node (ref "LED12") (pin "A") (pinfunction "A_A") (pintype "passive"))
      (node (ref "LED13") (pin "C") (pinfunction "C_C") (pintype "passive"))
      (node (ref "LED14") (pin "A") (pinfunction "A_A") (pintype "passive"))
      (node (ref "LED15") (pin "C") (pinfunction "C_C") (pintype "passive"))
      (node (ref "LED16") (pin "A") (pinfunction "A_A") (pintype "passive"))
      (node (ref "LED17") (pin "C") (pinfunction "C_C") (pintype "passive"))
      (node (ref "LED18") (pin "A") (pinfunction "A_A") (pintype "passive"))
      (node (ref "LED19") (pin "C") (pinfunction "C_C") (pintype "passive"))
      (node (ref "LED20") (pin "A") (pinfunction "A_A") (pintype "passive"))
    )
    (net (code "12") (name "Net-(H2-PadP6)") (class "Default")
      (node (ref "H2") (pin "P6") (pinfunction "P6_P6") (pintype "bidirectional"))
      (node (ref "LED10") (pin "C") (pinfunction "C_C") (pintype "passive"))
      (node (ref "LED129") (pin "A") (pinfunction "A_A") (pintype "passive"))
      (node (ref "LED130") (pin "C") (pinfunction "C_C") (pintype "passive"))
      (node (ref "LED70") (pin "C") (pinfunction "C_C") (pintype "passive"))
      (node (ref "LED71") (pin "A") (pinfunction "A_A") (pintype "passive"))
      (node (ref "LED9") (pin "A") (pinfunction "A_A") (pintype "passive"))
    )
    (net (code "13") (name "Net-(H3-PadP1)") (class "Default")
      (node (ref "H3") (pin "P1") (pinfunction "P1_P1") (pintype "bidirectional"))
      (node (ref "LED141") (pin "A") (pinfunction "A_A") (pintype "passive"))
      (node (ref "LED142") (pin "C") (pinfunction "C_C") (pintype "passive"))
      (node (ref "LED21") (pin "A") (pinfunction "A_A") (pintype "passive"))
      (node (ref "LED22") (pin "C") (pinfunction "C_C") (pintype "passive"))
      (node (ref "LED82") (pin "C") (pinfunction "C_C") (pintype "passive"))
      (node (ref "LED83") (pin "A") (pinfunction "A_A") (pintype "passive"))
    )
    (net (code "14") (name "Net-(H3-PadP2)") (class "Default")
      (node (ref "H3") (pin "P2") (pinfunction "P2_P2") (pintype "bidirectional"))
      (node (ref "LED143") (pin "A") (pinfunction "A_A") (pintype "passive"))
      (node (ref "LED144") (pin "C") (pinfunction "C_C") (pintype "passive"))
      (node (ref "LED23") (pin "A") (pinfunction "A_A") (pintype "passive"))
      (node (ref "LED24") (pin "C") (pinfunction "C_C") (pintype "passive"))
      (node (ref "LED84") (pin "C") (pinfunction "C_C") (pintype "passive"))
      (node (ref "LED85") (pin "A") (pinfunction "A_A") (pintype "passive"))
    )
    (net (code "15") (name "Net-(H3-PadP3)") (class "Default")
      (node (ref "H3") (pin "P3") (pinfunction "P3_P3") (pintype "bidirectional"))
      (node (ref "LED145") (pin "A") (pinfunction "A_A") (pintype "passive"))
      (node (ref "LED146") (pin "C") (pinfunction "C_C") (pintype "passive"))
      (node (ref "LED25") (pin "A") (pinfunction "A_A") (pintype "passive"))
      (node (ref "LED26") (pin "C") (pinfunction "C_C") (pintype "passive"))
      (node (ref "LED86") (pin "C") (pinfunction "C_C") (pintype "passive"))
      (node (ref "LED87") (pin "A") (pinfunction "A_A") (pintype "passive"))
    )
    (net (code "16") (name "Net-(H3-PadP4)") (class "Default")
      (node (ref "H3") (pin "P4") (pinfunction "P4_P4") (pintype "bidirectional"))
      (node (ref "LED137") (pin "A") (pinfunction "A_A") (pintype "passive"))
      (node (ref "LED138") (pin "C") (pinfunction "C_C") (pintype "passive"))
      (node (ref "LED17") (pin "A") (pinfunction "A_A") (pintype "passive"))
      (node (ref "LED18") (pin "C") (pinfunction "C_C") (pintype "passive"))
      (node (ref "LED78") (pin "C") (pinfunction "C_C") (pintype "passive"))
      (node (ref "LED79") (pin "A") (pinfunction "A_A") (pintype "passive"))
    )
    (net (code "17") (name "Net-(H3-PadP5)") (class "Default")
      (node (ref "H3") (pin "P5") (pinfunction "P5_P5") (pintype "bidirectional"))
      (node (ref "LED21") (pin "C") (pinfunction "C_C") (pintype "passive"))
      (node (ref "LED22") (pin "A") (pinfunction "A_A") (pintype "passive"))
      (node (ref "LED23") (pin "C") (pinfunction "C_C") (pintype "passive"))
      (node (ref "LED24") (pin "A") (pinfunction "A_A") (pintype "passive"))
      (node (ref "LED25") (pin "C") (pinfunction "C_C") (pintype "passive"))
      (node (ref "LED26") (pin "A") (pinfunction "A_A") (pintype "passive"))
      (node (ref "LED27") (pin "C") (pinfunction "C_C") (pintype "passive"))
      (node (ref "LED28") (pin "A") (pinfunction "A_A") (pintype "passive"))
      (node (ref "LED29") (pin "C") (pinfunction "C_C") (pintype "passive"))
      (node (ref "LED30") (pin "A") (pinfunction "A_A") (pintype "passive"))
    )
    (net (code "18") (name "Net-(H3-PadP6)") (class "Default")
      (node (ref "H3") (pin "P6") (pinfunction "P6_P6") (pintype "bidirectional"))
      (node (ref "LED139") (pin "A") (pinfunction "A_A") (pintype "passive"))
      (node (ref "LED140") (pin "C") (pinfunction "C_C") (pintype "passive"))
      (node (ref "LED19") (pin "A") (pinfunction "A_A") (pintype "passive"))
      (node (ref "LED20") (pin "C") (pinfunction "C_C") (pintype "passive"))
      (node (ref "LED80") (pin "C") (pinfunction "C_C") (pintype "passive"))
      (node (ref "LED81") (pin "A") (pinfunction "A_A") (pintype "passive"))
    )
    (net (code "19") (name "Net-(H4-PadP1)") (class "Default")
      (node (ref "H4") (pin "P1") (pinfunction "P1_P1") (pintype "bidirectional"))
      (node (ref "LED151") (pin "A") (pinfunction "A_A") (pintype "passive"))
      (node (ref "LED152") (pin "C") (pinfunction "C_C") (pintype "passive"))
      (node (ref "LED31") (pin "A") (pinfunction "A_A") (pintype "passive"))
      (node (ref "LED32") (pin "C") (pinfunction "C_C") (pintype "passive"))
      (node (ref "LED92") (pin "C") (pinfunction "C_C") (pintype "passive"))
      (node (ref "LED93") (pin "A") (pinfunction "A_A") (pintype "passive"))
    )
    (net (code "20") (name "Net-(H4-PadP2)") (class "Default")
      (node (ref "H4") (pin "P2") (pinfunction "P2_P2") (pintype "bidirectional"))
      (node (ref "LED153") (pin "A") (pinfunction "A_A") (pintype "passive"))
      (node (ref "LED154") (pin "C") (pinfunction "C_C") (pintype "passive"))
      (node (ref "LED33") (pin "A") (pinfunction "A_A") (pintype "passive"))
      (node (ref "LED34") (pin "C") (pinfunction "C_C") (pintype "passive"))
      (node (ref "LED94") (pin "C") (pinfunction "C_C") (pintype "passive"))
      (node (ref "LED95") (pin "A") (pinfunction "A_A") (pintype "passive"))
    )
    (net (code "21") (name "Net-(H4-PadP3)") (class "Default")
      (node (ref "H4") (pin "P3") (pinfunction "P3_P3") (pintype "bidirectional"))
      (node (ref "LED155") (pin "A") (pinfunction "A_A") (pintype "passive"))
      (node (ref "LED156") (pin "C") (pinfunction "C_C") (pintype "passive"))
      (node (ref "LED35") (pin "A") (pinfunction "A_A") (pintype "passive"))
      (node (ref "LED36") (pin "C") (pinfunction "C_C") (pintype "passive"))
      (node (ref "LED96") (pin "C") (pinfunction "C_C") (pintype "passive"))
      (node (ref "LED97") (pin "A") (pinfunction "A_A") (pintype "passive"))
    )
    (net (code "22") (name "Net-(H4-PadP4)") (class "Default")
      (node (ref "H4") (pin "P4") (pinfunction "P4_P4") (pintype "bidirectional"))
      (node (ref "LED147") (pin "A") (pinfunction "A_A") (pintype "passive"))
      (node (ref "LED148") (pin "C") (pinfunction "C_C") (pintype "passive"))
      (node (ref "LED27") (pin "A") (pinfunction "A_A") (pintype "passive"))
      (node (ref "LED28") (pin "C") (pinfunction "C_C") (pintype "passive"))
      (node (ref "LED88") (pin "C") (pinfunction "C_C") (pintype "passive"))
      (node (ref "LED89") (pin "A") (pinfunction "A_A") (pintype "passive"))
    )
    (net (code "23") (name "Net-(H4-PadP5)") (class "Default")
      (node (ref "H4") (pin "P5") (pinfunction "P5_P5") (pintype "bidirectional"))
      (node (ref "LED31") (pin "C") (pinfunction "C_C") (pintype "passive"))
      (node (ref "LED32") (pin "A") (pinfunction "A_A") (pintype "passive"))
      (node (ref "LED33") (pin "C") (pinfunction "C_C") (pintype "passive"))
      (node (ref "LED34") (pin "A") (pinfunction "A_A") (pintype "passive"))
      (node (ref "LED35") (pin "C") (pinfunction "C_C") (pintype "passive"))
      (node (ref "LED36") (pin "A") (pinfunction "A_A") (pintype "passive"))
      (node (ref "LED37") (pin "C") (pinfunction "C_C") (pintype "passive"))
      (node (ref "LED38") (pin "A") (pinfunction "A_A") (pintype "passive"))
      (node (ref "LED39") (pin "C") (pinfunction "C_C") (pintype "passive"))
      (node (ref "LED40") (pin "A") (pinfunction "A_A") (pintype "passive"))
    )
    (net (code "24") (name "Net-(H4-PadP6)") (class "Default")
      (node (ref "H4") (pin "P6") (pinfunction "P6_P6") (pintype "bidirectional"))
      (node (ref "LED149") (pin "A") (pinfunction "A_A") (pintype "passive"))
      (node (ref "LED150") (pin "C") (pinfunction "C_C") (pintype "passive"))
      (node (ref "LED29") (pin "A") (pinfunction "A_A") (pintype "passive"))
      (node (ref "LED30") (pin "C") (pinfunction "C_C") (pintype "passive"))
      (node (ref "LED90") (pin "C") (pinfunction "C_C") (pintype "passive"))
      (node (ref "LED91") (pin "A") (pinfunction "A_A") (pintype "passive"))
    )
    (net (code "25") (name "Net-(H5-PadP1)") (class "Default")
      (node (ref "H5") (pin "P1") (pinfunction "P1_P1") (pintype "bidirectional"))
      (node (ref "LED102") (pin "C") (pinfunction "C_C") (pintype "passive"))
      (node (ref "LED103") (pin "A") (pinfunction "A_A") (pintype "passive"))
      (node (ref "LED161") (pin "A") (pinfunction "A_A") (pintype "passive"))
      (node (ref "LED162") (pin "C") (pinfunction "C_C") (pintype "passive"))
      (node (ref "LED41") (pin "A") (pinfunction "A_A") (pintype "passive"))
      (node (ref "LED42") (pin "C") (pinfunction "C_C") (pintype "passive"))
    )
    (net (code "26") (name "Net-(H5-PadP2)") (class "Default")
      (node (ref "H5") (pin "P2") (pinfunction "P2_P2") (pintype "bidirectional"))
      (node (ref "LED104") (pin "C") (pinfunction "C_C") (pintype "passive"))
      (node (ref "LED105") (pin "A") (pinfunction "A_A") (pintype "passive"))
      (node (ref "LED163") (pin "A") (pinfunction "A_A") (pintype "passive"))
      (node (ref "LED164") (pin "C") (pinfunction "C_C") (pintype "passive"))
      (node (ref "LED43") (pin "A") (pinfunction "A_A") (pintype "passive"))
      (node (ref "LED44") (pin "C") (pinfunction "C_C") (pintype "passive"))
    )
    (net (code "27") (name "Net-(H5-PadP3)") (class "Default")
      (node (ref "H5") (pin "P3") (pinfunction "P3_P3") (pintype "bidirectional"))
      (node (ref "LED106") (pin "C") (pinfunction "C_C") (pintype "passive"))
      (node (ref "LED107") (pin "A") (pinfunction "A_A") (pintype "passive"))
      (node (ref "LED165") (pin "A") (pinfunction "A_A") (pintype "passive"))
      (node (ref "LED166") (pin "C") (pinfunction "C_C") (pintype "passive"))
      (node (ref "LED45") (pin "A") (pinfunction "A_A") (pintype "passive"))
      (node (ref "LED46") (pin "C") (pinfunction "C_C") (pintype "passive"))
    )
    (net (code "28") (name "Net-(H5-PadP4)") (class "Default")
      (node (ref "H5") (pin "P4") (pinfunction "P4_P4") (pintype "bidirectional"))
      (node (ref "LED157") (pin "A") (pinfunction "A_A") (pintype "passive"))
      (node (ref "LED158") (pin "C") (pinfunction "C_C") (pintype "passive"))
      (node (ref "LED37") (pin "A") (pinfunction "A_A") (pintype "passive"))
      (node (ref "LED38") (pin "C") (pinfunction "C_C") (pintype "passive"))
      (node (ref "LED98") (pin "C") (pinfunction "C_C") (pintype "passive"))
      (node (ref "LED99") (pin "A") (pinfunction "A_A") (pintype "passive"))
    )
    (net (code "29") (name "Net-(H5-PadP5)") (class "Default")
      (node (ref "H5") (pin "P5") (pinfunction "P5_P5") (pintype "bidirectional"))
      (node (ref "LED41") (pin "C") (pinfunction "C_C") (pintype "passive"))
      (node (ref "LED42") (pin "A") (pinfunction "A_A") (pintype "passive"))
      (node (ref "LED43") (pin "C") (pinfunction "C_C") (pintype "passive"))
      (node (ref "LED44") (pin "A") (pinfunction "A_A") (pintype "passive"))
      (node (ref "LED45") (pin "C") (pinfunction "C_C") (pintype "passive"))
      (node (ref "LED46") (pin "A") (pinfunction "A_A") (pintype "passive"))
      (node (ref "LED47") (pin "C") (pinfunction "C_C") (pintype "passive"))
      (node (ref "LED48") (pin "A") (pinfunction "A_A") (pintype "passive"))
      (node (ref "LED49") (pin "C") (pinfunction "C_C") (pintype "passive"))
      (node (ref "LED50") (pin "A") (pinfunction "A_A") (pintype "passive"))
    )
    (net (code "30") (name "Net-(H5-PadP6)") (class "Default")
      (node (ref "H5") (pin "P6") (pinfunction "P6_P6") (pintype "bidirectional"))
      (node (ref "LED100") (pin "C") (pinfunction "C_C") (pintype "passive"))
      (node (ref "LED101") (pin "A") (pinfunction "A_A") (pintype "passive"))
      (node (ref "LED159") (pin "A") (pinfunction "A_A") (pintype "passive"))
      (node (ref "LED160") (pin "C") (pinfunction "C_C") (pintype "passive"))
      (node (ref "LED39") (pin "A") (pinfunction "A_A") (pintype "passive"))
      (node (ref "LED40") (pin "C") (pinfunction "C_C") (pintype "passive"))
    )
    (net (code "31") (name "Net-(H6-PadP1)") (class "Default")
      (node (ref "H6") (pin "P1") (pinfunction "P1_P1") (pintype "bidirectional"))
      (node (ref "LED112") (pin "C") (pinfunction "C_C") (pintype "passive"))
      (node (ref "LED113") (pin "A") (pinfunction "A_A") (pintype "passive"))
      (node (ref "LED171") (pin "A") (pinfunction "A_A") (pintype "passive"))
      (node (ref "LED172") (pin "C") (pinfunction "C_C") (pintype "passive"))
      (node (ref "LED51") (pin "A") (pinfunction "A_A") (pintype "passive"))
      (node (ref "LED52") (pin "C") (pinfunction "C_C") (pintype "passive"))
    )
    (net (code "32") (name "Net-(H6-PadP2)") (class "Default")
      (node (ref "H6") (pin "P2") (pinfunction "P2_P2") (pintype "bidirectional"))
      (node (ref "LED114") (pin "C") (pinfunction "C_C") (pintype "passive"))
      (node (ref "LED115") (pin "A") (pinfunction "A_A") (pintype "passive"))
      (node (ref "LED173") (pin "A") (pinfunction "A_A") (pintype "passive"))
      (node (ref "LED174") (pin "C") (pinfunction "C_C") (pintype "passive"))
      (node (ref "LED53") (pin "A") (pinfunction "A_A") (pintype "passive"))
      (node (ref "LED54") (pin "C") (pinfunction "C_C") (pintype "passive"))
    )
    (net (code "33") (name "Net-(H6-PadP3)") (class "Default")
      (node (ref "H6") (pin "P3") (pinfunction "P3_P3") (pintype "bidirectional"))
      (node (ref "LED116") (pin "C") (pinfunction "C_C") (pintype "passive"))
      (node (ref "LED117") (pin "A") (pinfunction "A_A") (pintype "passive"))
      (node (ref "LED175") (pin "A") (pinfunction "A_A") (pintype "passive"))
      (node (ref "LED176") (pin "C") (pinfunction "C_C") (pintype "passive"))
      (node (ref "LED55") (pin "A") (pinfunction "A_A") (pintype "passive"))
      (node (ref "LED56") (pin "C") (pinfunction "C_C") (pintype "passive"))
    )
    (net (code "34") (name "Net-(H6-PadP4)") (class "Default")
      (node (ref "H6") (pin "P4") (pinfunction "P4_P4") (pintype "bidirectional"))
      (node (ref "LED108") (pin "C") (pinfunction "C_C") (pintype "passive"))
      (node (ref "LED109") (pin "A") (pinfunction "A_A") (pintype "passive"))
      (node (ref "LED167") (pin "A") (pinfunction "A_A") (pintype "passive"))
      (node (ref "LED168") (pin "C") (pinfunction "C_C") (pintype "passive"))
      (node (ref "LED47") (pin "A") (pinfunction "A_A") (pintype "passive"))
      (node (ref "LED48") (pin "C") (pinfunction "C_C") (pintype "passive"))
    )
    (net (code "35") (name "Net-(H6-PadP5)") (class "Default")
      (node (ref "H6") (pin "P5") (pinfunction "P5_P5") (pintype "bidirectional"))
      (node (ref "LED51") (pin "C") (pinfunction "C_C") (pintype "passive"))
      (node (ref "LED52") (pin "A") (pinfunction "A_A") (pintype "passive"))
      (node (ref "LED53") (pin "C") (pinfunction "C_C") (pintype "passive"))
      (node (ref "LED54") (pin "A") (pinfunction "A_A") (pintype "passive"))
      (node (ref "LED55") (pin "C") (pinfunction "C_C") (pintype "passive"))
      (node (ref "LED56") (pin "A") (pinfunction "A_A") (pintype "passive"))
      (node (ref "LED57") (pin "C") (pinfunction "C_C") (pintype "passive"))
      (node (ref "LED58") (pin "A") (pinfunction "A_A") (pintype "passive"))
      (node (ref "LED59") (pin "C") (pinfunction "C_C") (pintype "passive"))
      (node (ref "LED60") (pin "A") (pinfunction "A_A") (pintype "passive"))
    )
    (net (code "36") (name "Net-(H6-PadP6)") (class "Default")
      (node (ref "H6") (pin "P6") (pinfunction "P6_P6") (pintype "bidirectional"))
      (node (ref "LED110") (pin "C") (pinfunction "C_C") (pintype "passive"))
      (node (ref "LED111") (pin "A") (pinfunction "A_A") (pintype "passive"))
      (node (ref "LED169") (pin "A") (pinfunction "A_A") (pintype "passive"))
      (node (ref "LED170") (pin "C") (pinfunction "C_C") (pintype "passive"))
      (node (ref "LED49") (pin "A") (pinfunction "A_A") (pintype "passive"))
      (node (ref "LED50") (pin "C") (pinfunction "C_C") (pintype "passive"))
    )
    (net (code "37") (name "Net-(H7-PadP1)") (class "Default")
      (node (ref "H7") (pin "P1") (pinfunction "P1_P1") (pintype "bidirectional"))
      (node (ref "LED62") (pin "A") (pinfunction "A_A") (pintype "passive"))
      (node (ref "LED63") (pin "C") (pinfunction "C_C") (pintype "passive"))
      (node (ref "LED64") (pin "A") (pinfunction "A_A") (pintype "passive"))
      (node (ref "LED65") (pin "C") (pinfunction "C_C") (pintype "passive"))
      (node (ref "LED66") (pin "A") (pinfunction "A_A") (pintype "passive"))
      (node (ref "LED67") (pin "C") (pinfunction "C_C") (pintype "passive"))
      (node (ref "LED68") (pin "A") (pinfunction "A_A") (pintype "passive"))
      (node (ref "LED69") (pin "C") (pinfunction "C_C") (pintype "passive"))
      (node (ref "LED70") (pin "A") (pinfunction "A_A") (pintype "passive"))
      (node (ref "LED71") (pin "C") (pinfunction "C_C") (pintype "passive"))
    )
    (net (code "38") (name "Net-(H7-PadP2)") (class "Default")
      (node (ref "H7") (pin "P2") (pinfunction "P2_P2") (pintype "bidirectional"))
      (node (ref "LED171") (pin "C") (pinfunction "C_C") (pintype "passive"))
      (node (ref "LED172") (pin "A") (pinfunction "A_A") (pintype "passive"))
      (node (ref "LED173") (pin "C") (pinfunction "C_C") (pintype "passive"))
      (node (ref "LED174") (pin "A") (pinfunction "A_A") (pintype "passive"))
      (node (ref "LED175") (pin "C") (pinfunction "C_C") (pintype "passive"))
      (node (ref "LED176") (pin "A") (pinfunction "A_A") (pintype "passive"))
      (node (ref "LED177") (pin "C") (pinfunction "C_C") (pintype "passive"))
      (node (ref "LED178") (pin "A") (pinfunction "A_A") (pintype "passive"))
      (node (ref "LED179") (pin "C") (pinfunction "C_C") (pintype "passive"))
      (node (ref "LED180") (pin "A") (pinfunction "A_A") (pintype "passive"))
    )
    (net (code "39") (name "Net-(H7-PadP3)") (class "Default")
      (node (ref "H7") (pin "P3") (pinfunction "P3_P3") (pintype "bidirectional"))
      (node (ref "LED72") (pin "A") (pinfunction "A_A") (pintype "passive"))
      (node (ref "LED73") (pin "C") (pinfunction "C_C") (pintype "passive"))
      (node (ref "LED74") (pin "A") (pinfunction "A_A") (pintype "passive"))
      (node (ref "LED75") (pin "C") (pinfunction "C_C") (pintype "passive"))
      (node (ref "LED76") (pin "A") (pinfunction "A_A") (pintype "passive"))
      (node (ref "LED77") (pin "C") (pinfunction "C_C") (pintype "passive"))
      (node (ref "LED78") (pin "A") (pinfunction "A_A") (pintype "passive"))
      (node (ref "LED79") (pin "C") (pinfunction "C_C") (pintype "passive"))
      (node (ref "LED80") (pin "A") (pinfunction "A_A") (pintype "passive"))
      (node (ref "LED81") (pin "C") (pinfunction "C_C") (pintype "passive"))
    )
    (net (code "40") (name "Net-(H7-PadP4)") (class "Default")
      (node (ref "H7") (pin "P4") (pinfunction "P4_P4") (pintype "bidirectional"))
      (node (ref "LED121") (pin "C") (pinfunction "C_C") (pintype "passive"))
      (node (ref "LED122") (pin "A") (pinfunction "A_A") (pintype "passive"))
      (node (ref "LED123") (pin "C") (pinfunction "C_C") (pintype "passive"))
      (node (ref "LED124") (pin "A") (pinfunction "A_A") (pintype "passive"))
      (node (ref "LED125") (pin "C") (pinfunction "C_C") (pintype "passive"))
      (node (ref "LED126") (pin "A") (pinfunction "A_A") (pintype "passive"))
      (node (ref "LED127") (pin "C") (pinfunction "C_C") (pintype "passive"))
      (node (ref "LED128") (pin "A") (pinfunction "A_A") (pintype "passive"))
      (node (ref "LED129") (pin "C") (pinfunction "C_C") (pintype "passive"))
      (node (ref "LED130") (pin "A") (pinfunction "A_A") (pintype "passive"))
    )
    (net (code "41") (name "Net-(H8-PadP1)") (class "Default")
      (node (ref "H8") (pin "P1") (pinfunction "P1_P1") (pintype "bidirectional"))
      (node (ref "LED82") (pin "A") (pinfunction "A_A") (pintype "passive"))
      (node (ref "LED83") (pin "C") (pinfunction "C_C") (pintype "passive"))
      (node (ref "LED84") (pin "A") (pinfunction "A_A") (pintype "passive"))
      (node (ref "LED85") (pin "C") (pinfunction "C_C") (pintype "passive"))
      (node (ref "LED86") (pin "A") (pinfunction "A_A") (pintype "passive"))
      (node (ref "LED87") (pin "C") (pinfunction "C_C") (pintype "passive"))
      (node (ref "LED88") (pin "A") (pinfunction "A_A") (pintype "passive"))
      (node (ref "LED89") (pin "C") (pinfunction "C_C") (pintype "passive"))
      (node (ref "LED90") (pin "A") (pinfunction "A_A") (pintype "passive"))
      (node (ref "LED91") (pin "C") (pinfunction "C_C") (pintype "passive"))
    )
    (net (code "42") (name "Net-(H8-PadP2)") (class "Default")
      (node (ref "H8") (pin "P2") (pinfunction "P2_P2") (pintype "bidirectional"))
      (node (ref "LED131") (pin "C") (pinfunction "C_C") (pintype "passive"))
      (node (ref "LED132") (pin "A") (pinfunction "A_A") (pintype "passive"))
      (node (ref "LED133") (pin "C") (pinfunction "C_C") (pintype "passive"))
      (node (ref "LED134") (pin "A") (pinfunction "A_A") (pintype "passive"))
      (node (ref "LED135") (pin "C") (pinfunction "C_C") (pintype "passive"))
      (node (ref "LED136") (pin "A") (pinfunction "A_A") (pintype "passive"))
      (node (ref "LED137") (pin "C") (pinfunction "C_C") (pintype "passive"))
      (node (ref "LED138") (pin "A") (pinfunction "A_A") (pintype "passive"))
      (node (ref "LED139") (pin "C") (pinfunction "C_C") (pintype "passive"))
      (node (ref "LED140") (pin "A") (pinfunction "A_A") (pintype "passive"))
    )
    (net (code "43") (name "Net-(H8-PadP3)") (class "Default")
      (node (ref "H8") (pin "P3") (pinfunction "P3_P3") (pintype "bidirectional"))
      (node (ref "LED100") (pin "A") (pinfunction "A_A") (pintype "passive"))
      (node (ref "LED101") (pin "C") (pinfunction "C_C") (pintype "passive"))
      (node (ref "LED92") (pin "A") (pinfunction "A_A") (pintype "passive"))
      (node (ref "LED93") (pin "C") (pinfunction "C_C") (pintype "passive"))
      (node (ref "LED94") (pin "A") (pinfunction "A_A") (pintype "passive"))
      (node (ref "LED95") (pin "C") (pinfunction "C_C") (pintype "passive"))
      (node (ref "LED96") (pin "A") (pinfunction "A_A") (pintype "passive"))
      (node (ref "LED97") (pin "C") (pinfunction "C_C") (pintype "passive"))
      (node (ref "LED98") (pin "A") (pinfunction "A_A") (pintype "passive"))
      (node (ref "LED99") (pin "C") (pinfunction "C_C") (pintype "passive"))
    )
    (net (code "44") (name "Net-(H8-PadP4)") (class "Default")
      (node (ref "H8") (pin "P4") (pinfunction "P4_P4") (pintype "bidirectional"))
      (node (ref "LED141") (pin "C") (pinfunction "C_C") (pintype "passive"))
      (node (ref "LED142") (pin "A") (pinfunction "A_A") (pintype "passive"))
      (node (ref "LED143") (pin "C") (pinfunction "C_C") (pintype "passive"))
      (node (ref "LED144") (pin "A") (pinfunction "A_A") (pintype "passive"))
      (node (ref "LED145") (pin "C") (pinfunction "C_C") (pintype "passive"))
      (node (ref "LED146") (pin "A") (pinfunction "A_A") (pintype "passive"))
      (node (ref "LED147") (pin "C") (pinfunction "C_C") (pintype "passive"))
      (node (ref "LED148") (pin "A") (pinfunction "A_A") (pintype "passive"))
      (node (ref "LED149") (pin "C") (pinfunction "C_C") (pintype "passive"))
      (node (ref "LED150") (pin "A") (pinfunction "A_A") (pintype "passive"))
    )
    (net (code "45") (name "Net-(H9-PadP1)") (class "Default")
      (node (ref "H9") (pin "P1") (pinfunction "P1_P1") (pintype "bidirectional"))
      (node (ref "LED102") (pin "A") (pinfunction "A_A") (pintype "passive"))
      (node (ref "LED103") (pin "C") (pinfunction "C_C") (pintype "passive"))
      (node (ref "LED104") (pin "A") (pinfunction "A_A") (pintype "passive"))
      (node (ref "LED105") (pin "C") (pinfunction "C_C") (pintype "passive"))
      (node (ref "LED106") (pin "A") (pinfunction "A_A") (pintype "passive"))
      (node (ref "LED107") (pin "C") (pinfunction "C_C") (pintype "passive"))
      (node (ref "LED108") (pin "A") (pinfunction "A_A") (pintype "passive"))
      (node (ref "LED109") (pin "C") (pinfunction "C_C") (pintype "passive"))
      (node (ref "LED110") (pin "A") (pinfunction "A_A") (pintype "passive"))
      (node (ref "LED111") (pin "C") (pinfunction "C_C") (pintype "passive"))
    )
    (net (code "46") (name "Net-(H9-PadP2)") (class "Default")
      (node (ref "H9") (pin "P2") (pinfunction "P2_P2") (pintype "bidirectional"))
      (node (ref "LED151") (pin "C") (pinfunction "C_C") (pintype "passive"))
      (node (ref "LED152") (pin "A") (pinfunction "A_A") (pintype "passive"))
      (node (ref "LED153") (pin "C") (pinfunction "C_C") (pintype "passive"))
      (node (ref "LED154") (pin "A") (pinfunction "A_A") (pintype "passive"))
      (node (ref "LED155") (pin "C") (pinfunction "C_C") (pintype "passive"))
      (node (ref "LED156") (pin "A") (pinfunction "A_A") (pintype "passive"))
      (node (ref "LED157") (pin "C") (pinfunction "C_C") (pintype "passive"))
      (node (ref "LED158") (pin "A") (pinfunction "A_A") (pintype "passive"))
      (node (ref "LED159") (pin "C") (pinfunction "C_C") (pintype "passive"))
      (node (ref "LED160") (pin "A") (pinfunction "A_A") (pintype "passive"))
    )
    (net (code "47") (name "Net-(H9-PadP3)") (class "Default")
      (node (ref "H9") (pin "P3") (pinfunction "P3_P3") (pintype "bidirectional"))
      (node (ref "LED112") (pin "A") (pinfunction "A_A") (pintype "passive"))
      (node (ref "LED113") (pin "C") (pinfunction "C_C") (pintype "passive"))
      (node (ref "LED114") (pin "A") (pinfunction "A_A") (pintype "passive"))
      (node (ref "LED115") (pin "C") (pinfunction "C_C") (pintype "passive"))
      (node (ref "LED116") (pin "A") (pinfunction "A_A") (pintype "passive"))
      (node (ref "LED117") (pin "C") (pinfunction "C_C") (pintype "passive"))
      (node (ref "LED118") (pin "A") (pinfunction "A_A") (pintype "passive"))
      (node (ref "LED119") (pin "C") (pinfunction "C_C") (pintype "passive"))
      (node (ref "LED120") (pin "A") (pinfunction "A_A") (pintype "passive"))
      (node (ref "LED61") (pin "C") (pinfunction "C_C") (pintype "passive"))
    )
    (net (code "48") (name "Net-(H9-PadP4)") (class "Default")
      (node (ref "H9") (pin "P4") (pinfunction "P4_P4") (pintype "bidirectional"))
      (node (ref "LED161") (pin "C") (pinfunction "C_C") (pintype "passive"))
      (node (ref "LED162") (pin "A") (pinfunction "A_A") (pintype "passive"))
      (node (ref "LED163") (pin "C") (pinfunction "C_C") (pintype "passive"))
      (node (ref "LED164") (pin "A") (pinfunction "A_A") (pintype "passive"))
      (node (ref "LED165") (pin "C") (pinfunction "C_C") (pintype "passive"))
      (node (ref "LED166") (pin "A") (pinfunction "A_A") (pintype "passive"))
      (node (ref "LED167") (pin "C") (pinfunction "C_C") (pintype "passive"))
      (node (ref "LED168") (pin "A") (pinfunction "A_A") (pintype "passive"))
      (node (ref "LED169") (pin "C") (pinfunction "C_C") (pintype "passive"))
      (node (ref "LED170") (pin "A") (pinfunction "A_A") (pintype "passive"))
    )
  )
)
